# MCU.net
KiCad netlist of a schematic drawn in Altium Designer
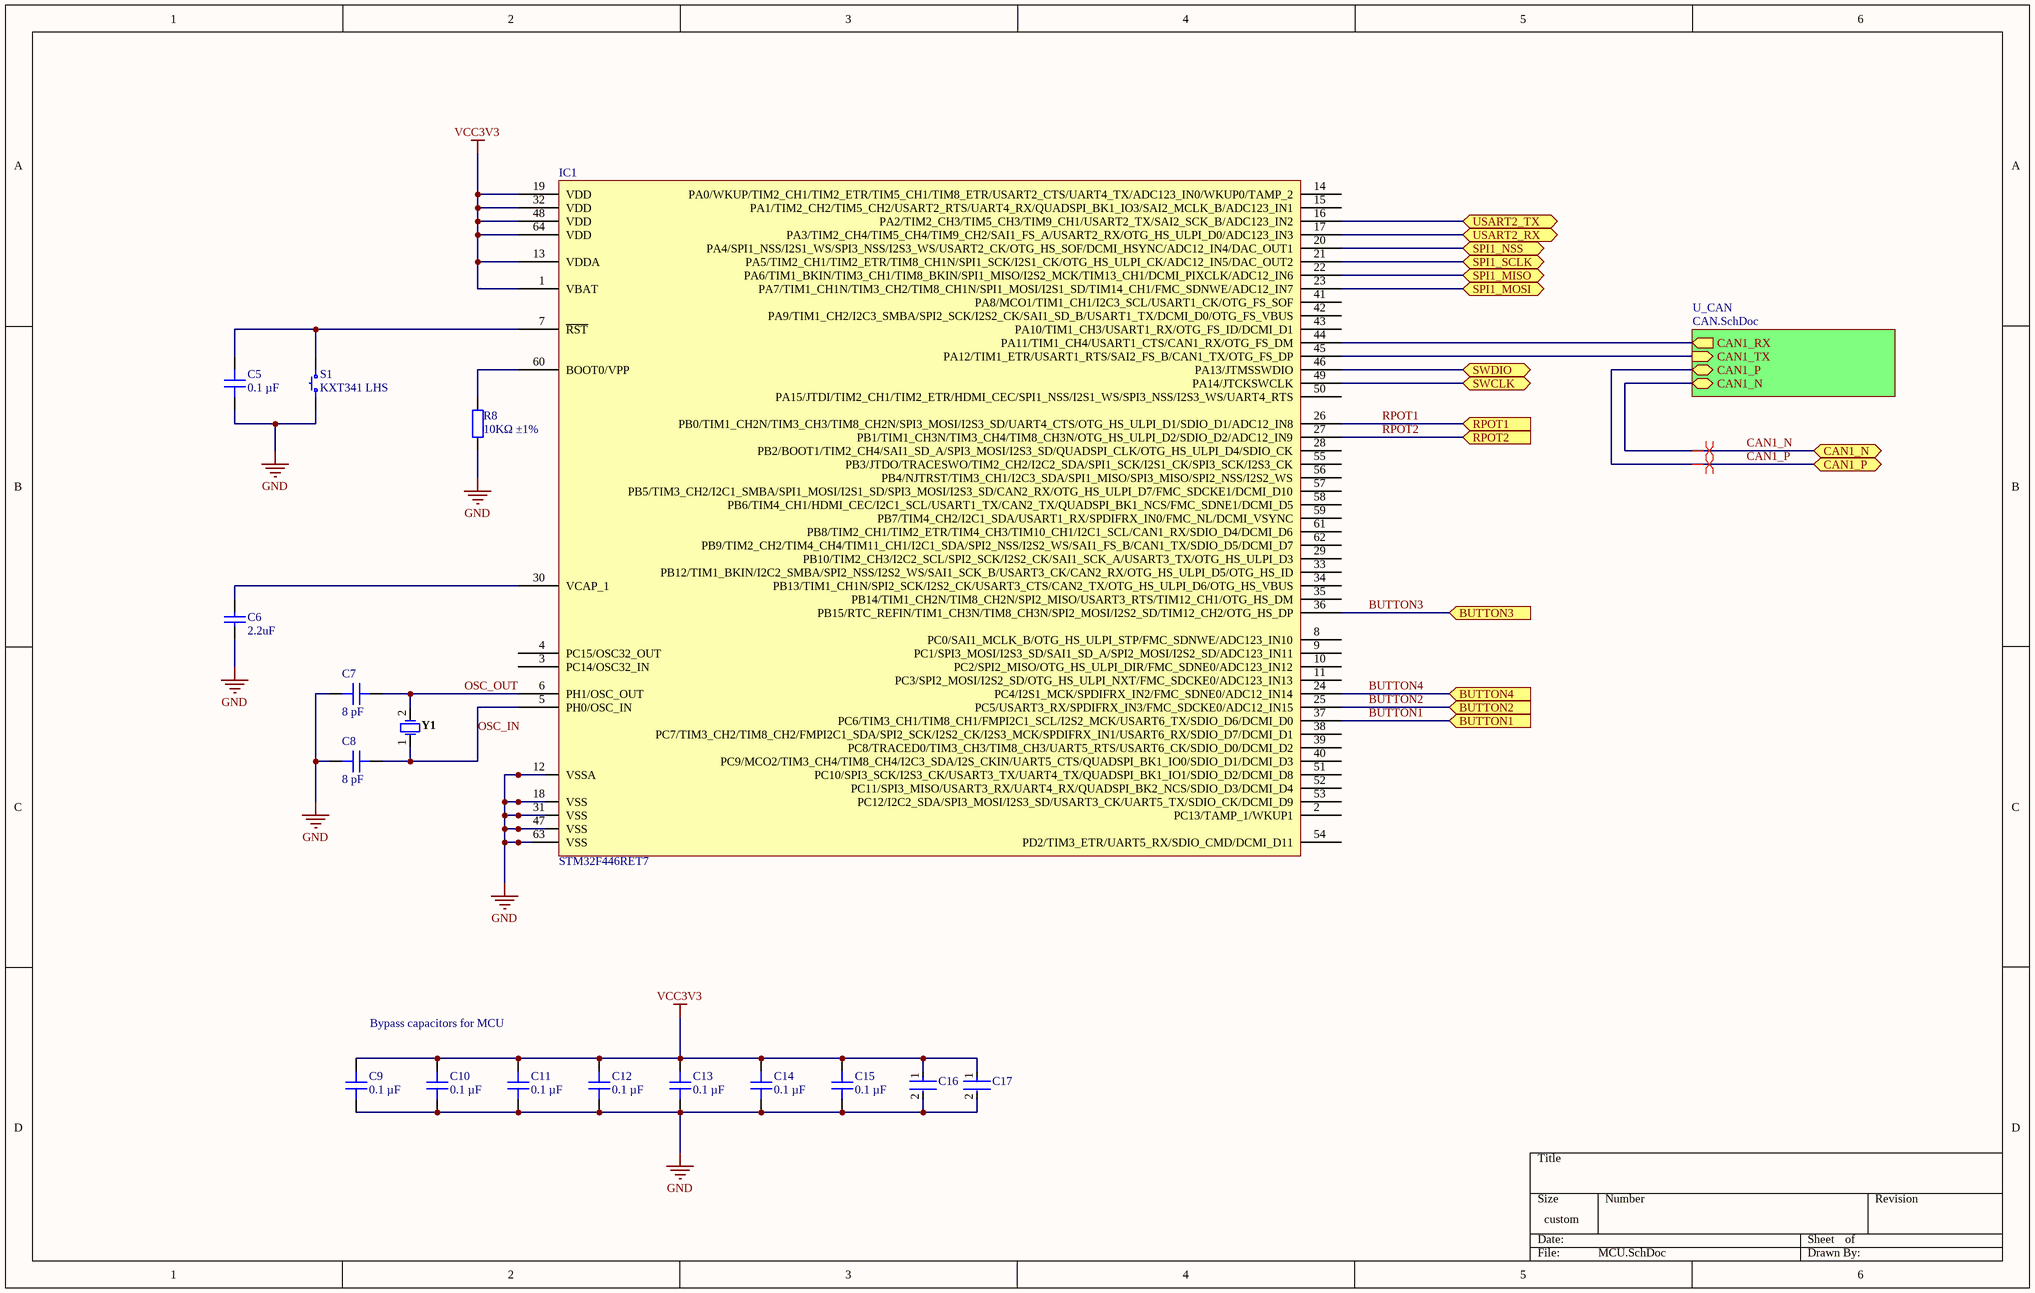
[diagram p0: MCU.SchDoc]

(export (version "E")
  (design (tool "Eeschema 10.0.6"))
  (components
    (comp (ref "C5")
      (value "0.1 µF")
      (footprint "CAP 0402_1005")
      (description "CAP CER 0402 0.1UF 16V X7R 10%")
      (fields (field (name "PART NUMBER") "C0402C104K4RECAUTO") (field (name "MANUFACTURER") "KEMET"))
      (libsource (lib "Celestial Altium Library - altium_library") (part "Capacitor"))
    )
    (comp (ref "C6")
      (value "2.2uF")
      (footprint "0603_C")
      (description "Chip capacitors")
      (fields
        (field (name "MANUFACTURER") "Samsung Electro-Mechanics")
        (field (name "PARTNUMBER") "CL10A225KO8NNNC")
      )
      (libsource (lib "Cap") (part "0603 2.2uF (225) 10% 16V"))
    )
    (comp (ref "C7")
      (value "8 pF")
      (footprint "CAP 0402_1005")
      (description "CAP CER 8PF 50V NP0 0402")
      (fields
        (field (name "PART NUMBER") "C1005NP01H080D050BA")
        (field (name "MANUFACTURER") "TDK Corporation")
      )
      (libsource (lib "Celestial Altium Library - altium_library") (part "Capacitor"))
    )
    (comp (ref "C8")
      (value "8 pF")
      (footprint "CAP 0402_1005")
      (description "CAP CER 8PF 50V NP0 0402")
      (fields
        (field (name "PART NUMBER") "C1005NP01H080D050BA")
        (field (name "MANUFACTURER") "TDK Corporation")
      )
      (libsource (lib "Celestial Altium Library - altium_library") (part "Capacitor"))
    )
    (comp (ref "C9")
      (value "0.1 µF")
      (footprint "CAP 0402_1005")
      (description "CAP CER 0402 0.1UF 16V X7R 10%")
      (fields (field (name "PART NUMBER") "C0402C104K4RECAUTO") (field (name "MANUFACTURER") "KEMET"))
      (libsource (lib "Celestial Altium Library - altium_library") (part "Capacitor"))
    )
    (comp (ref "C10")
      (value "0.1 µF")
      (footprint "CAP 0402_1005")
      (description "CAP CER 0402 0.1UF 16V X7R 10%")
      (fields (field (name "PART NUMBER") "C0402C104K4RECAUTO") (field (name "MANUFACTURER") "KEMET"))
      (libsource (lib "Celestial Altium Library - altium_library") (part "Capacitor"))
    )
    (comp (ref "C11")
      (value "0.1 µF")
      (footprint "CAP 0402_1005")
      (description "CAP CER 0402 0.1UF 16V X7R 10%")
      (fields (field (name "PART NUMBER") "C0402C104K4RECAUTO") (field (name "MANUFACTURER") "KEMET"))
      (libsource (lib "Celestial Altium Library - altium_library") (part "Capacitor"))
    )
    (comp (ref "C12")
      (value "0.1 µF")
      (footprint "CAP 0402_1005")
      (description "CAP CER 0402 0.1UF 16V X7R 10%")
      (fields (field (name "PART NUMBER") "C0402C104K4RECAUTO") (field (name "MANUFACTURER") "KEMET"))
      (libsource (lib "Celestial Altium Library - altium_library") (part "Capacitor"))
    )
    (comp (ref "C13")
      (value "0.1 µF")
      (footprint "CAP 0402_1005")
      (description "CAP CER 0402 0.1UF 16V X7R 10%")
      (fields (field (name "PART NUMBER") "C0402C104K4RECAUTO") (field (name "MANUFACTURER") "KEMET"))
      (libsource (lib "Celestial Altium Library - altium_library") (part "Capacitor"))
    )
    (comp (ref "C14")
      (value "0.1 µF")
      (footprint "CAP 0402_1005")
      (description "CAP CER 0402 0.1UF 16V X7R 10%")
      (fields (field (name "PART NUMBER") "C0402C104K4RECAUTO") (field (name "MANUFACTURER") "KEMET"))
      (libsource (lib "Celestial Altium Library - altium_library") (part "Capacitor"))
    )
    (comp (ref "C15")
      (value "0.1 µF")
      (footprint "CAP 0402_1005")
      (description "CAP CER 0402 0.1UF 16V X7R 10%")
      (fields (field (name "PART NUMBER") "C0402C104K4RECAUTO") (field (name "MANUFACTURER") "KEMET"))
      (libsource (lib "Celestial Altium Library - altium_library") (part "Capacitor"))
    )
    (comp (ref "C16")
      (value "CGB2A1X5R1A105K033BC")
      (footprint "FP-CGB2A-IPC_B")
      (description "Multilayer Ceramic Capacitors 1uF ±10% 10V X5R SMD 0402")
      (fields (field (name "TOLERANCE") "10%"))
      (libsource (lib "Altium Content Vault") (part "11868f565c42a9108669ba33697ecf6"))
    )
    (comp (ref "C17")
      (value "CGB2A1X5R1A105K033BC")
      (footprint "FP-CGB2A-IPC_B")
      (description "Multilayer Ceramic Capacitors 1uF ±10% 10V X5R SMD 0402")
      (fields (field (name "TOLERANCE") "10%"))
      (libsource (lib "Altium Content Vault") (part "11868f565c42a9108669ba33697ecf6"))
    )
    (comp (ref "IC1")
      (value "STM32F446RET7")
      (footprint "ST LQFP-64 10X10MM")
      (description "IC MCU 32BIT 512KB FLASH 64LQFP")
      (fields (field (name "MANUFACTURER") "STMicroelectronics"))
      (libsource (lib "Celestial Altium Library - altium_library") (part "ST STM32F446 64PIN"))
    )
    (comp (ref "R8")
      (value "10KΩ ±1%")
      (footprint "0402_R")
      (description "Chip resistor")
      (fields (field (name "MANUFACTURER") "Uniroyal Elec") (field (name "PARTNUMBER") "0402WGF1002TCE"))
      (libsource (lib "RES") (part "0402 10K (1002) 1%"))
    )
    (comp (ref "S1")
      (value "KXT341 LHS")
      (footprint "C&K KXT3")
      (description "SWITCH TACTILE SPST-NO 0.02A 15V")
      (fields (field (name "MANUFACTURER") "C&K"))
      (libsource (lib "Celestial Altium Library - altium_library") (part "SPST-NO 2 PIN"))
    )
    (comp (ref "Y1")
      (value "NX3225GD-8MHZ-STD-CRA-3")
      (footprint "NDK-NX3225GD-8MHZ-STD-CRA-3_V")
      (description "Crystal Unit, 8 MHz, 8 pF, -40 to 150 degC, 2-Pin SMD, RoHS, Tape and Reel")
      (fields (field (name "MANUFACTURER") "NDK"))
      (libsource (lib "Altium Content Vault") (part "XTAL-1-2-2"))
    )
  )
  (nets
    (net (code "1") (name "/BUTTON1") (class "Default")
      (node (ref "IC1") (pin "37") (pinfunction "PC6/TIM3_CH1/TIM8_CH1/FMPI2C1_SCL/I2S2_MCK/USART6_TX/SDIO_D6/DCMI_D0_37") (pintype "passive"))
    )
    (net (code "2") (name "/BUTTON2") (class "Default")
      (node (ref "IC1") (pin "25") (pinfunction "PC5/USART3_RX/SPDIFRX_IN3/FMC_SDCKE0/ADC12_IN15_25") (pintype "passive"))
    )
    (net (code "3") (name "/BUTTON3") (class "Default")
      (node (ref "IC1") (pin "36") (pinfunction "PB15/RTC_REFIN/TIM1_CH3N/TIM8_CH3N/SPI2_MOSI/I2S2_SD/TIM12_CH2/OTG_HS_DP_36") (pintype "passive"))
    )
    (net (code "4") (name "/BUTTON4") (class "Default")
      (node (ref "IC1") (pin "24") (pinfunction "PC4/I2S1_MCK/SPDIFRX_IN2/FMC_SDNE0/ADC12_IN14_24") (pintype "passive"))
    )
    (net (code "7") (name "/CAN1_RX") (class "Default")
      (node (ref "IC1") (pin "44") (pinfunction "PA11/TIM1_CH4/USART1_CTS/CAN1_RX/OTG_FS_DM_44") (pintype "passive"))
    )
    (net (code "8") (name "/CAN1_TX") (class "Default")
      (node (ref "IC1") (pin "45") (pinfunction "PA12/TIM1_ETR/USART1_RTS/SAI2_FS_B/CAN1_TX/OTG_FS_DP_45") (pintype "passive"))
    )
    (net (code "9") (name "/OSC_IN") (class "Default")
      (node (ref "C8") (pin "1") (pinfunction "1_1") (pintype "passive"))
      (node (ref "IC1") (pin "5") (pinfunction "PH0/OSC_IN_5") (pintype "passive"))
      (node (ref "Y1") (pin "1") (pinfunction "1_1") (pintype "passive"))
    )
    (net (code "10") (name "/OSC_OUT") (class "Default")
      (node (ref "C7") (pin "1") (pinfunction "1_1") (pintype "passive"))
      (node (ref "IC1") (pin "6") (pinfunction "PH1/OSC_OUT_6") (pintype "passive"))
      (node (ref "Y1") (pin "2") (pinfunction "2_2") (pintype "passive"))
    )
    (net (code "11") (name "/RPOT1") (class "Default")
      (node (ref "IC1") (pin "26") (pinfunction "PB0/TIM1_CH2N/TIM3_CH3/TIM8_CH2N/SPI3_MOSI/I2S3_SD/UART4_CTS/OTG_HS_ULPI_D1/SDIO_D1/ADC12_IN8_26") (pintype "passive"))
    )
    (net (code "12") (name "/RPOT2") (class "Default")
      (node (ref "IC1") (pin "27") (pinfunction "PB1/TIM1_CH3N/TIM3_CH4/TIM8_CH3N/OTG_HS_ULPI_D2/SDIO_D2/ADC12_IN9_27") (pintype "passive"))
    )
    (net (code "13") (name "/SPI1_MISO") (class "Default")
      (node (ref "IC1") (pin "22") (pinfunction "PA6/TIM1_BKIN/TIM3_CH1/TIM8_BKIN/SPI1_MISO/I2S2_MCK/TIM13_CH1/DCMI_PIXCLK/ADC12_IN6_22") (pintype "passive"))
    )
    (net (code "14") (name "/SPI1_MOSI") (class "Default")
      (node (ref "IC1") (pin "23") (pinfunction "PA7/TIM1_CH1N/TIM3_CH2/TIM8_CH1N/SPI1_MOSI/I2S1_SD/TIM14_CH1/FMC_SDNWE/ADC12_IN7_23") (pintype "passive"))
    )
    (net (code "15") (name "/SPI1_NSS") (class "Default")
      (node (ref "IC1") (pin "20") (pinfunction "PA4/SPI1_NSS/I2S1_WS/SPI3_NSS/I2S3_WS/USART2_CK/OTG_HS_SOF/DCMI_HSYNC/ADC12_IN4/DAC_OUT1_20") (pintype "passive"))
    )
    (net (code "16") (name "/SPI1_SCLK") (class "Default")
      (node (ref "IC1") (pin "21") (pinfunction "PA5/TIM2_CH1/TIM2_ETR/TIM8_CH1N/SPI1_SCK/I2S1_CK/OTG_HS_ULPI_CK/ADC12_IN5/DAC_OUT2_21") (pintype "passive"))
    )
    (net (code "17") (name "/SWCLK") (class "Default")
      (node (ref "IC1") (pin "49") (pinfunction "PA14/JTCKSWCLK_49") (pintype "passive"))
    )
    (net (code "18") (name "/SWDIO") (class "Default")
      (node (ref "IC1") (pin "46") (pinfunction "PA13/JTMSSWDIO_46") (pintype "passive"))
    )
    (net (code "19") (name "/USART2_RX") (class "Default")
      (node (ref "IC1") (pin "17") (pinfunction "PA3/TIM2_CH4/TIM5_CH4/TIM9_CH2/SAI1_FS_A/USART2_RX/OTG_HS_ULPI_D0/ADC123_IN3_17") (pintype "passive"))
    )
    (net (code "20") (name "/USART2_TX") (class "Default")
      (node (ref "IC1") (pin "16") (pinfunction "PA2/TIM2_CH3/TIM5_CH3/TIM9_CH1/USART2_TX/SAI2_SCK_B/ADC123_IN2_16") (pintype "passive"))
    )
    (net (code "21") (name "GND") (class "Default")
      (node (ref "C10") (pin "1") (pinfunction "1_1") (pintype "passive"))
      (node (ref "C11") (pin "1") (pinfunction "1_1") (pintype "passive"))
      (node (ref "C12") (pin "1") (pinfunction "1_1") (pintype "passive"))
      (node (ref "C13") (pin "1") (pinfunction "1_1") (pintype "passive"))
      (node (ref "C14") (pin "1") (pinfunction "1_1") (pintype "passive"))
      (node (ref "C15") (pin "1") (pinfunction "1_1") (pintype "passive"))
      (node (ref "C16") (pin "2") (pinfunction "2_2") (pintype "passive"))
      (node (ref "C17") (pin "2") (pinfunction "2_2") (pintype "passive"))
      (node (ref "C5") (pin "1") (pinfunction "1_1") (pintype "passive"))
      (node (ref "C6") (pin "1") (pinfunction "1_1") (pintype "passive"))
      (node (ref "C7") (pin "2") (pinfunction "2_2") (pintype "passive"))
      (node (ref "C8") (pin "2") (pinfunction "2_2") (pintype "passive"))
      (node (ref "C9") (pin "1") (pinfunction "1_1") (pintype "passive"))
      (node (ref "IC1") (pin "12") (pinfunction "VSSA_12") (pintype "passive"))
      (node (ref "IC1") (pin "18") (pinfunction "VSS_18") (pintype "passive"))
      (node (ref "IC1") (pin "31") (pinfunction "VSS_31") (pintype "passive"))
      (node (ref "IC1") (pin "47") (pinfunction "VSS_47") (pintype "passive"))
      (node (ref "IC1") (pin "63") (pinfunction "VSS_63") (pintype "passive"))
      (node (ref "R8") (pin "1") (pinfunction "1_1") (pintype "passive"))
      (node (ref "S1") (pin "1") (pinfunction "1_1") (pintype "passive"))
    )
    (net (code "22") (name "Net-(IC1-BOOT0{slash}VPP)") (class "Default")
      (node (ref "IC1") (pin "60") (pinfunction "BOOT0/VPP_60") (pintype "passive"))
      (node (ref "R8") (pin "2") (pinfunction "2_2") (pintype "passive"))
    )
    (net (code "23") (name "Net-(IC1-VCAP_1)") (class "Default")
      (node (ref "C6") (pin "2") (pinfunction "2_2") (pintype "passive"))
      (node (ref "IC1") (pin "30") (pinfunction "VCAP_1_30") (pintype "passive"))
    )
    (net (code "24") (name "Net-(IC1-~{RST})") (class "Default")
      (node (ref "C5") (pin "2") (pinfunction "2_2") (pintype "passive"))
      (node (ref "IC1") (pin "7") (pinfunction "~{RST}_7") (pintype "passive"))
      (node (ref "S1") (pin "2") (pinfunction "2_2") (pintype "passive"))
    )
    (net (code "25") (name "VCC3V3") (class "Default")
      (node (ref "C10") (pin "2") (pinfunction "2_2") (pintype "passive"))
      (node (ref "C11") (pin "2") (pinfunction "2_2") (pintype "passive"))
      (node (ref "C12") (pin "2") (pinfunction "2_2") (pintype "passive"))
      (node (ref "C13") (pin "2") (pinfunction "2_2") (pintype "passive"))
      (node (ref "C14") (pin "2") (pinfunction "2_2") (pintype "passive"))
      (node (ref "C15") (pin "2") (pinfunction "2_2") (pintype "passive"))
      (node (ref "C16") (pin "1") (pinfunction "1_1") (pintype "passive"))
      (node (ref "C17") (pin "1") (pinfunction "1_1") (pintype "passive"))
      (node (ref "C9") (pin "2") (pinfunction "2_2") (pintype "passive"))
      (node (ref "IC1") (pin "1") (pinfunction "VBAT_1") (pintype "passive"))
      (node (ref "IC1") (pin "13") (pinfunction "VDDA_13") (pintype "passive"))
      (node (ref "IC1") (pin "19") (pinfunction "VDD_19") (pintype "passive"))
      (node (ref "IC1") (pin "32") (pinfunction "VDD_32") (pintype "passive"))
      (node (ref "IC1") (pin "48") (pinfunction "VDD_48") (pintype "passive"))
      (node (ref "IC1") (pin "64") (pinfunction "VDD_64") (pintype "passive"))
    )
    (net (code "26") (name "unconnected-(IC1-PA0{slash}WKUP{slash}TIM2_CH1{slash}TIM2_ETR{slash}TIM5_CH1{slash}TIM8_ETR{slash}USART2_CTS{slash}UART4_TX{slash}ADC123_IN0{slash}WKUP0{slash}TAMP_2-Pad14)") (class "Default")
      (node (ref "IC1") (pin "14") (pinfunction "PA0/WKUP/TIM2_CH1/TIM2_ETR/TIM5_CH1/TIM8_ETR/USART2_CTS/UART4_TX/ADC123_IN0/WKUP0/TAMP_2_14") (pintype "passive"))
    )
    (net (code "27") (name "unconnected-(IC1-PA1{slash}TIM2_CH2{slash}TIM5_CH2{slash}USART2_RTS{slash}UART4_RX{slash}QUADSPI_BK1_IO3{slash}SAI2_MCLK_B{slash}ADC123_IN1-Pad15)") (class "Default")
      (node (ref "IC1") (pin "15") (pinfunction "PA1/TIM2_CH2/TIM5_CH2/USART2_RTS/UART4_RX/QUADSPI_BK1_IO3/SAI2_MCLK_B/ADC123_IN1_15") (pintype "passive"))
    )
    (net (code "28") (name "unconnected-(IC1-PA8{slash}MCO1{slash}TIM1_CH1{slash}I2C3_SCL{slash}USART1_CK{slash}OTG_FS_SOF-Pad41)") (class "Default")
      (node (ref "IC1") (pin "41") (pinfunction "PA8/MCO1/TIM1_CH1/I2C3_SCL/USART1_CK/OTG_FS_SOF_41") (pintype "passive"))
    )
    (net (code "29") (name "unconnected-(IC1-PA9{slash}TIM1_CH2{slash}I2C3_SMBA{slash}SPI2_SCK{slash}I2S2_CK{slash}SAI1_SD_B{slash}USART1_TX{slash}DCMI_D0{slash}OTG_FS_VBUS-Pad42)") (class "Default")
      (node (ref "IC1") (pin "42") (pinfunction "PA9/TIM1_CH2/I2C3_SMBA/SPI2_SCK/I2S2_CK/SAI1_SD_B/USART1_TX/DCMI_D0/OTG_FS_VBUS_42") (pintype "passive"))
    )
    (net (code "30") (name "unconnected-(IC1-PA10{slash}TIM1_CH3{slash}USART1_RX{slash}OTG_FS_ID{slash}DCMI_D1-Pad43)") (class "Default")
      (node (ref "IC1") (pin "43") (pinfunction "PA10/TIM1_CH3/USART1_RX/OTG_FS_ID/DCMI_D1_43") (pintype "passive"))
    )
    (net (code "31") (name "unconnected-(IC1-PA15{slash}JTDI{slash}TIM2_CH1{slash}TIM2_ETR{slash}HDMI_CEC{slash}SPI1_NSS{slash}I2S1_WS{slash}SPI3_NSS{slash}I2S3_WS{slash}UART4_RTS-Pad50)") (class "Default")
      (node (ref "IC1") (pin "50") (pinfunction "PA15/JTDI/TIM2_CH1/TIM2_ETR/HDMI_CEC/SPI1_NSS/I2S1_WS/SPI3_NSS/I2S3_WS/UART4_RTS_50") (pintype "passive"))
    )
    (net (code "32") (name "unconnected-(IC1-PB2{slash}BOOT1{slash}TIM2_CH4{slash}SAI1_SD_A{slash}SPI3_MOSI{slash}I2S3_SD{slash}QUADSPI_CLK{slash}OTG_HS_ULPI_D4{slash}SDIO_CK-Pad28)") (class "Default")
      (node (ref "IC1") (pin "28") (pinfunction "PB2/BOOT1/TIM2_CH4/SAI1_SD_A/SPI3_MOSI/I2S3_SD/QUADSPI_CLK/OTG_HS_ULPI_D4/SDIO_CK_28") (pintype "passive"))
    )
    (net (code "33") (name "unconnected-(IC1-PB3{slash}JTDO{slash}TRACESWO{slash}TIM2_CH2{slash}I2C2_SDA{slash}SPI1_SCK{slash}I2S1_CK{slash}SPI3_SCK{slash}I2S3_CK-Pad55)") (class "Default")
      (node (ref "IC1") (pin "55") (pinfunction "PB3/JTDO/TRACESWO/TIM2_CH2/I2C2_SDA/SPI1_SCK/I2S1_CK/SPI3_SCK/I2S3_CK_55") (pintype "passive"))
    )
    (net (code "34") (name "unconnected-(IC1-PB4{slash}NJTRST{slash}TIM3_CH1{slash}I2C3_SDA{slash}SPI1_MISO{slash}SPI3_MISO{slash}SPI2_NSS{slash}I2S2_WS-Pad56)") (class "Default")
      (node (ref "IC1") (pin "56") (pinfunction "PB4/NJTRST/TIM3_CH1/I2C3_SDA/SPI1_MISO/SPI3_MISO/SPI2_NSS/I2S2_WS_56") (pintype "passive"))
    )
    (net (code "35") (name "unconnected-(IC1-PB5{slash}TIM3_CH2{slash}I2C1_SMBA{slash}SPI1_MOSI{slash}I2S1_SD{slash}SPI3_MOSI{slash}I2S3_SD{slash}CAN2_RX{slash}OTG_HS_ULPI_D7{slash}FMC_SDCKE1{slash}DCMI_D10-Pad57)") (class "Default")
      (node (ref "IC1") (pin "57") (pinfunction "PB5/TIM3_CH2/I2C1_SMBA/SPI1_MOSI/I2S1_SD/SPI3_MOSI/I2S3_SD/CAN2_RX/OTG_HS_ULPI_D7/FMC_SDCKE1/DCMI_D10_57") (pintype "passive"))
    )
    (net (code "36") (name "unconnected-(IC1-PB6{slash}TIM4_CH1{slash}HDMI_CEC{slash}I2C1_SCL{slash}USART1_TX{slash}CAN2_TX{slash}QUADSPI_BK1_NCS{slash}FMC_SDNE1{slash}DCMI_D5-Pad58)") (class "Default")
      (node (ref "IC1") (pin "58") (pinfunction "PB6/TIM4_CH1/HDMI_CEC/I2C1_SCL/USART1_TX/CAN2_TX/QUADSPI_BK1_NCS/FMC_SDNE1/DCMI_D5_58") (pintype "passive"))
    )
    (net (code "37") (name "unconnected-(IC1-PB7{slash}TIM4_CH2{slash}I2C1_SDA{slash}USART1_RX{slash}SPDIFRX_IN0{slash}FMC_NL{slash}DCMI_VSYNC-Pad59)") (class "Default")
      (node (ref "IC1") (pin "59") (pinfunction "PB7/TIM4_CH2/I2C1_SDA/USART1_RX/SPDIFRX_IN0/FMC_NL/DCMI_VSYNC_59") (pintype "passive"))
    )
    (net (code "38") (name "unconnected-(IC1-PB8{slash}TIM2_CH1{slash}TIM2_ETR{slash}TIM4_CH3{slash}TIM10_CH1{slash}I2C1_SCL{slash}CAN1_RX{slash}SDIO_D4{slash}DCMI_D6-Pad61)") (class "Default")
      (node (ref "IC1") (pin "61") (pinfunction "PB8/TIM2_CH1/TIM2_ETR/TIM4_CH3/TIM10_CH1/I2C1_SCL/CAN1_RX/SDIO_D4/DCMI_D6_61") (pintype "passive"))
    )
    (net (code "39") (name "unconnected-(IC1-PB9{slash}TIM2_CH2{slash}TIM4_CH4{slash}TIM11_CH1{slash}I2C1_SDA{slash}SPI2_NSS{slash}I2S2_WS{slash}SAI1_FS_B{slash}CAN1_TX{slash}SDIO_D5{slash}DCMI_D7-Pad62)") (class "Default")
      (node (ref "IC1") (pin "62") (pinfunction "PB9/TIM2_CH2/TIM4_CH4/TIM11_CH1/I2C1_SDA/SPI2_NSS/I2S2_WS/SAI1_FS_B/CAN1_TX/SDIO_D5/DCMI_D7_62") (pintype "passive"))
    )
    (net (code "40") (name "unconnected-(IC1-PB10{slash}TIM2_CH3{slash}I2C2_SCL{slash}SPI2_SCK{slash}I2S2_CK{slash}SAI1_SCK_A{slash}USART3_TX{slash}OTG_HS_ULPI_D3-Pad29)") (class "Default")
      (node (ref "IC1") (pin "29") (pinfunction "PB10/TIM2_CH3/I2C2_SCL/SPI2_SCK/I2S2_CK/SAI1_SCK_A/USART3_TX/OTG_HS_ULPI_D3_29") (pintype "passive"))
    )
    (net (code "41") (name "unconnected-(IC1-PB12{slash}TIM1_BKIN{slash}I2C2_SMBA{slash}SPI2_NSS{slash}I2S2_WS{slash}SAI1_SCK_B{slash}USART3_CK{slash}CAN2_RX{slash}OTG_HS_ULPI_D5{slash}OTG_HS_ID-Pad33)") (class "Default")
      (node (ref "IC1") (pin "33") (pinfunction "PB12/TIM1_BKIN/I2C2_SMBA/SPI2_NSS/I2S2_WS/SAI1_SCK_B/USART3_CK/CAN2_RX/OTG_HS_ULPI_D5/OTG_HS_ID_33") (pintype "passive"))
    )
    (net (code "42") (name "unconnected-(IC1-PB13{slash}TIM1_CH1N{slash}SPI2_SCK{slash}I2S2_CK{slash}USART3_CTS{slash}CAN2_TX{slash}OTG_HS_ULPI_D6{slash}OTG_HS_VBUS-Pad34)") (class "Default")
      (node (ref "IC1") (pin "34") (pinfunction "PB13/TIM1_CH1N/SPI2_SCK/I2S2_CK/USART3_CTS/CAN2_TX/OTG_HS_ULPI_D6/OTG_HS_VBUS_34") (pintype "passive"))
    )
    (net (code "43") (name "unconnected-(IC1-PB14{slash}TIM1_CH2N{slash}TIM8_CH2N{slash}SPI2_MISO{slash}USART3_RTS{slash}TIM12_CH1{slash}OTG_HS_DM-Pad35)") (class "Default")
      (node (ref "IC1") (pin "35") (pinfunction "PB14/TIM1_CH2N/TIM8_CH2N/SPI2_MISO/USART3_RTS/TIM12_CH1/OTG_HS_DM_35") (pintype "passive"))
    )
    (net (code "44") (name "unconnected-(IC1-PC0{slash}SAI1_MCLK_B{slash}OTG_HS_ULPI_STP{slash}FMC_SDNWE{slash}ADC123_IN10-Pad8)") (class "Default")
      (node (ref "IC1") (pin "8") (pinfunction "PC0/SAI1_MCLK_B/OTG_HS_ULPI_STP/FMC_SDNWE/ADC123_IN10_8") (pintype "passive"))
    )
    (net (code "45") (name "unconnected-(IC1-PC1{slash}SPI3_MOSI{slash}I2S3_SD{slash}SAI1_SD_A{slash}SPI2_MOSI{slash}I2S2_SD{slash}ADC123_IN11-Pad9)") (class "Default")
      (node (ref "IC1") (pin "9") (pinfunction "PC1/SPI3_MOSI/I2S3_SD/SAI1_SD_A/SPI2_MOSI/I2S2_SD/ADC123_IN11_9") (pintype "passive"))
    )
    (net (code "46") (name "unconnected-(IC1-PC2{slash}SPI2_MISO{slash}OTG_HS_ULPI_DIR{slash}FMC_SDNE0{slash}ADC123_IN12-Pad10)") (class "Default")
      (node (ref "IC1") (pin "10") (pinfunction "PC2/SPI2_MISO/OTG_HS_ULPI_DIR/FMC_SDNE0/ADC123_IN12_10") (pintype "passive"))
    )
    (net (code "47") (name "unconnected-(IC1-PC3{slash}SPI2_MOSI{slash}I2S2_SD{slash}OTG_HS_ULPI_NXT{slash}FMC_SDCKE0{slash}ADC123_IN13-Pad11)") (class "Default")
      (node (ref "IC1") (pin "11") (pinfunction "PC3/SPI2_MOSI/I2S2_SD/OTG_HS_ULPI_NXT/FMC_SDCKE0/ADC123_IN13_11") (pintype "passive"))
    )
    (net (code "48") (name "unconnected-(IC1-PC7{slash}TIM3_CH2{slash}TIM8_CH2{slash}FMPI2C1_SDA{slash}SPI2_SCK{slash}I2S2_CK{slash}I2S3_MCK{slash}SPDIFRX_IN1{slash}USART6_RX{slash}SDIO_D7{slash}DCMI_D1-Pad38)") (class "Default")
      (node (ref "IC1") (pin "38") (pinfunction "PC7/TIM3_CH2/TIM8_CH2/FMPI2C1_SDA/SPI2_SCK/I2S2_CK/I2S3_MCK/SPDIFRX_IN1/USART6_RX/SDIO_D7/DCMI_D1_38") (pintype "passive"))
    )
    (net (code "49") (name "unconnected-(IC1-PC8{slash}TRACED0{slash}TIM3_CH3{slash}TIM8_CH3{slash}UART5_RTS{slash}USART6_CK{slash}SDIO_D0{slash}DCMI_D2-Pad39)") (class "Default")
      (node (ref "IC1") (pin "39") (pinfunction "PC8/TRACED0/TIM3_CH3/TIM8_CH3/UART5_RTS/USART6_CK/SDIO_D0/DCMI_D2_39") (pintype "passive"))
    )
    (net (code "50") (name "unconnected-(IC1-PC9{slash}MCO2{slash}TIM3_CH4{slash}TIM8_CH4{slash}I2C3_SDA{slash}I2S_CKIN{slash}UART5_CTS{slash}QUADSPI_BK1_IO0{slash}SDIO_D1{slash}DCMI_D3-Pad40)") (class "Default")
      (node (ref "IC1") (pin "40") (pinfunction "PC9/MCO2/TIM3_CH4/TIM8_CH4/I2C3_SDA/I2S_CKIN/UART5_CTS/QUADSPI_BK1_IO0/SDIO_D1/DCMI_D3_40") (pintype "passive"))
    )
    (net (code "51") (name "unconnected-(IC1-PC10{slash}SPI3_SCK{slash}I2S3_CK{slash}USART3_TX{slash}UART4_TX{slash}QUADSPI_BK1_IO1{slash}SDIO_D2{slash}DCMI_D8-Pad51)") (class "Default")
      (node (ref "IC1") (pin "51") (pinfunction "PC10/SPI3_SCK/I2S3_CK/USART3_TX/UART4_TX/QUADSPI_BK1_IO1/SDIO_D2/DCMI_D8_51") (pintype "passive"))
    )
    (net (code "52") (name "unconnected-(IC1-PC11{slash}SPI3_MISO{slash}USART3_RX{slash}UART4_RX{slash}QUADSPI_BK2_NCS{slash}SDIO_D3{slash}DCMI_D4-Pad52)") (class "Default")
      (node (ref "IC1") (pin "52") (pinfunction "PC11/SPI3_MISO/USART3_RX/UART4_RX/QUADSPI_BK2_NCS/SDIO_D3/DCMI_D4_52") (pintype "passive"))
    )
    (net (code "53") (name "unconnected-(IC1-PC12{slash}I2C2_SDA{slash}SPI3_MOSI{slash}I2S3_SD{slash}USART3_CK{slash}UART5_TX{slash}SDIO_CK{slash}DCMI_D9-Pad53)") (class "Default")
      (node (ref "IC1") (pin "53") (pinfunction "PC12/I2C2_SDA/SPI3_MOSI/I2S3_SD/USART3_CK/UART5_TX/SDIO_CK/DCMI_D9_53") (pintype "passive"))
    )
    (net (code "54") (name "unconnected-(IC1-PC13{slash}TAMP_1{slash}WKUP1-Pad2)") (class "Default")
      (node (ref "IC1") (pin "2") (pinfunction "PC13/TAMP_1/WKUP1_2") (pintype "passive"))
    )
    (net (code "55") (name "unconnected-(IC1-PC14{slash}OSC32_IN-Pad3)") (class "Default")
      (node (ref "IC1") (pin "3") (pinfunction "PC14/OSC32_IN_3") (pintype "passive"))
    )
    (net (code "56") (name "unconnected-(IC1-PC15{slash}OSC32_OUT-Pad4)") (class "Default")
      (node (ref "IC1") (pin "4") (pinfunction "PC15/OSC32_OUT_4") (pintype "passive"))
    )
    (net (code "57") (name "unconnected-(IC1-PD2{slash}TIM3_ETR{slash}UART5_RX{slash}SDIO_CMD{slash}DCMI_D11-Pad54)") (class "Default")
      (node (ref "IC1") (pin "54") (pinfunction "PD2/TIM3_ETR/UART5_RX/SDIO_CMD/DCMI_D11_54") (pintype "passive"))
    )
  )
)
